# BatteryPoweredSchematic.net
KiCad netlist of a schematic drawn in Altium Designer
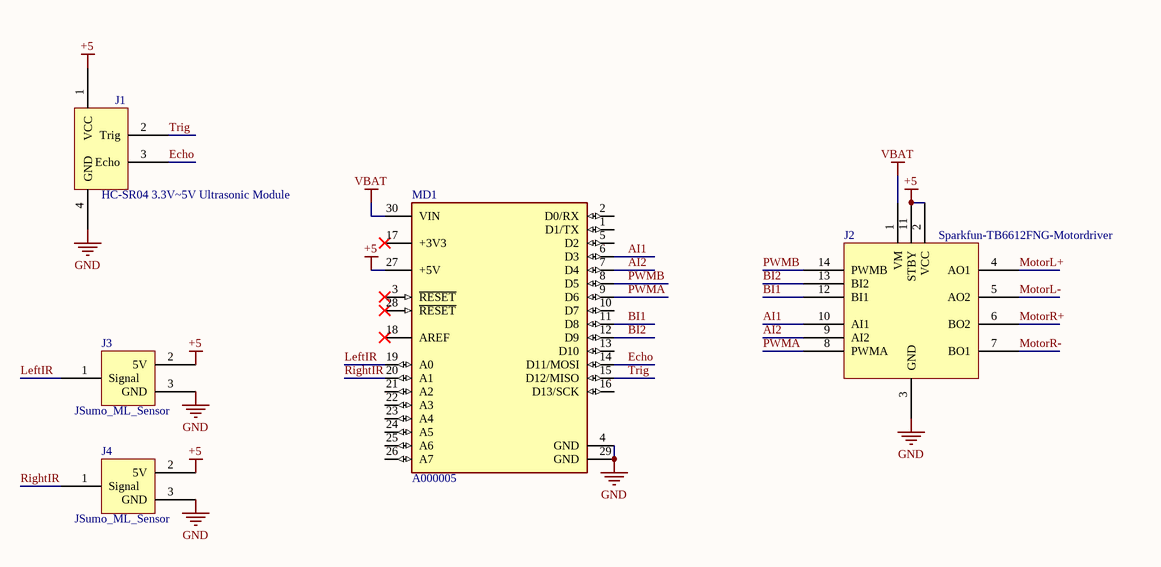
[diagram p0: BatteryPoweredSchematic.SchDoc]

(export (version "E")
  (design (tool "Eeschema 10.0.6"))
  (components
    (comp (ref "J1")
      (value "HC-SR04 3.3V~5V Ultrasonic Module")
      (libsource (lib "Matteo Jahshan") (part "HC-SR04 3.3V~5V Ultrasonic Module"))
    )
    (comp (ref "J2")
      (value "Sparkfun-TB6612FNG-Motordriver")
      (libsource (lib "Matteo Jahshan") (part "Sparkfun-TB6612FNG-Motordriver-Symbol-1"))
    )
    (comp (ref "J3")
      (value "JSumo_ML_Sensor")
      (libsource (lib "Matteo Jahshan") (part "JSumo_ML_Sensor-Symbol-1"))
    )
    (comp (ref "J4")
      (value "JSumo_ML_Sensor")
      (libsource (lib "Matteo Jahshan") (part "JSumo_ML_Sensor-Symbol-1"))
    )
    (comp (ref "MD1")
      (value "A000005")
      (footprint "FP-A000005-MFG")
      (description "ARDUINO NANO ATMEGA328 EVAL BRD")
      (libsource (lib "Altium Content Vault") (part "d190c066e99afd1c6882cf92e11b2cc"))
    )
  )
  (nets
    (net (code "1") (name "+5") (class "Default")
      (node (ref "J1") (pin "1") (pinfunction "VCC_1") (pintype "passive"))
      (node (ref "J2") (pin "11") (pinfunction "STBY_11") (pintype "passive"))
      (node (ref "J2") (pin "2") (pinfunction "VCC_2") (pintype "passive"))
      (node (ref "J3") (pin "2") (pinfunction "5V_2") (pintype "passive"))
      (node (ref "J4") (pin "2") (pinfunction "5V_2") (pintype "passive"))
      (node (ref "MD1") (pin "27") (pinfunction "+5V_27") (pintype "power_in"))
    )
    (net (code "2") (name "/AI1") (class "Default")
      (node (ref "J2") (pin "10") (pinfunction "AI1_10") (pintype "passive"))
      (node (ref "MD1") (pin "6") (pinfunction "D3_6") (pintype "bidirectional"))
    )
    (net (code "3") (name "/AI2") (class "Default")
      (node (ref "J2") (pin "9") (pinfunction "AI2_9") (pintype "passive"))
      (node (ref "MD1") (pin "7") (pinfunction "D4_7") (pintype "bidirectional"))
    )
    (net (code "4") (name "/BI1") (class "Default")
      (node (ref "J2") (pin "12") (pinfunction "BI1_12") (pintype "passive"))
      (node (ref "MD1") (pin "11") (pinfunction "D8_11") (pintype "bidirectional"))
    )
    (net (code "5") (name "/BI2") (class "Default")
      (node (ref "J2") (pin "13") (pinfunction "BI2_13") (pintype "passive"))
      (node (ref "MD1") (pin "12") (pinfunction "D9_12") (pintype "bidirectional"))
    )
    (net (code "6") (name "/Echo") (class "Default")
      (node (ref "J1") (pin "3") (pinfunction "Echo_3") (pintype "passive"))
      (node (ref "MD1") (pin "14") (pinfunction "D11/MOSI_14") (pintype "bidirectional"))
    )
    (net (code "7") (name "/LeftIR") (class "Default")
      (node (ref "J3") (pin "1") (pinfunction "Signal_1") (pintype "passive"))
      (node (ref "MD1") (pin "19") (pinfunction "A0_19") (pintype "bidirectional"))
    )
    (net (code "8") (name "/MotorL+") (class "Default")
      (node (ref "J2") (pin "4") (pinfunction "AO1_4") (pintype "passive"))
    )
    (net (code "9") (name "/MotorL-") (class "Default")
      (node (ref "J2") (pin "5") (pinfunction "AO2_5") (pintype "passive"))
    )
    (net (code "10") (name "/MotorR+") (class "Default")
      (node (ref "J2") (pin "6") (pinfunction "BO2_6") (pintype "passive"))
    )
    (net (code "11") (name "/MotorR-") (class "Default")
      (node (ref "J2") (pin "7") (pinfunction "BO1_7") (pintype "passive"))
    )
    (net (code "12") (name "/PWMA") (class "Default")
      (node (ref "J2") (pin "8") (pinfunction "PWMA_8") (pintype "passive"))
      (node (ref "MD1") (pin "9") (pinfunction "D6_9") (pintype "bidirectional"))
    )
    (net (code "13") (name "/PWMB") (class "Default")
      (node (ref "J2") (pin "14") (pinfunction "PWMB_14") (pintype "passive"))
      (node (ref "MD1") (pin "8") (pinfunction "D5_8") (pintype "bidirectional"))
    )
    (net (code "14") (name "/RightIR") (class "Default")
      (node (ref "J4") (pin "1") (pinfunction "Signal_1") (pintype "passive"))
      (node (ref "MD1") (pin "20") (pinfunction "A1_20") (pintype "bidirectional"))
    )
    (net (code "15") (name "/Trig") (class "Default")
      (node (ref "J1") (pin "2") (pinfunction "Trig_2") (pintype "passive"))
      (node (ref "MD1") (pin "15") (pinfunction "D12/MISO_15") (pintype "bidirectional"))
    )
    (net (code "16") (name "GND") (class "Default")
      (node (ref "J1") (pin "4") (pinfunction "GND_4") (pintype "passive"))
      (node (ref "J2") (pin "3") (pinfunction "GND_3") (pintype "passive"))
      (node (ref "J3") (pin "3") (pinfunction "GND_3") (pintype "passive"))
      (node (ref "J4") (pin "3") (pinfunction "GND_3") (pintype "passive"))
      (node (ref "MD1") (pin "29") (pinfunction "GND_29") (pintype "power_in"))
      (node (ref "MD1") (pin "4") (pinfunction "GND_4") (pintype "power_in"))
    )
    (net (code "17") (name "VBAT") (class "Default")
      (node (ref "J2") (pin "1") (pinfunction "VM_1") (pintype "passive"))
      (node (ref "MD1") (pin "30") (pinfunction "VIN_30") (pintype "power_in"))
    )
    (net (code "18") (name "unconnected-(MD1-+3V3-Pad17)") (class "Default")
      (node (ref "MD1") (pin "17") (pinfunction "+3V3_17") (pintype "power_in+no_connect"))
    )
    (net (code "19") (name "unconnected-(MD1-A2-Pad21)") (class "Default")
      (node (ref "MD1") (pin "21") (pinfunction "A2_21") (pintype "bidirectional"))
    )
    (net (code "20") (name "unconnected-(MD1-A3-Pad22)") (class "Default")
      (node (ref "MD1") (pin "22") (pinfunction "A3_22") (pintype "bidirectional"))
    )
    (net (code "21") (name "unconnected-(MD1-A4-Pad23)") (class "Default")
      (node (ref "MD1") (pin "23") (pinfunction "A4_23") (pintype "bidirectional"))
    )
    (net (code "22") (name "unconnected-(MD1-A5-Pad24)") (class "Default")
      (node (ref "MD1") (pin "24") (pinfunction "A5_24") (pintype "bidirectional"))
    )
    (net (code "23") (name "unconnected-(MD1-A6-Pad25)") (class "Default")
      (node (ref "MD1") (pin "25") (pinfunction "A6_25") (pintype "bidirectional"))
    )
    (net (code "24") (name "unconnected-(MD1-A7-Pad26)") (class "Default")
      (node (ref "MD1") (pin "26") (pinfunction "A7_26") (pintype "bidirectional"))
    )
    (net (code "25") (name "unconnected-(MD1-AREF-Pad18)") (class "Default")
      (node (ref "MD1") (pin "18") (pinfunction "AREF_18") (pintype "passive+no_connect"))
    )
    (net (code "26") (name "unconnected-(MD1-D0{slash}RX-Pad2)") (class "Default")
      (node (ref "MD1") (pin "2") (pinfunction "D0/RX_2") (pintype "bidirectional"))
    )
    (net (code "27") (name "unconnected-(MD1-D1{slash}TX-Pad1)") (class "Default")
      (node (ref "MD1") (pin "1") (pinfunction "D1/TX_1") (pintype "bidirectional"))
    )
    (net (code "28") (name "unconnected-(MD1-D2-Pad5)") (class "Default")
      (node (ref "MD1") (pin "5") (pinfunction "D2_5") (pintype "bidirectional"))
    )
    (net (code "29") (name "unconnected-(MD1-D7-Pad10)") (class "Default")
      (node (ref "MD1") (pin "10") (pinfunction "D7_10") (pintype "bidirectional"))
    )
    (net (code "30") (name "unconnected-(MD1-D10-Pad13)") (class "Default")
      (node (ref "MD1") (pin "13") (pinfunction "D10_13") (pintype "bidirectional"))
    )
    (net (code "31") (name "unconnected-(MD1-D13{slash}SCK-Pad16)") (class "Default")
      (node (ref "MD1") (pin "16") (pinfunction "D13/SCK_16") (pintype "bidirectional"))
    )
    (net (code "32") (name "unconnected-(MD1-~{RESET}-Pad3)") (class "Default")
      (node (ref "MD1") (pin "3") (pinfunction "~{RESET}_3") (pintype "input+no_connect"))
    )
    (net (code "33") (name "unconnected-(MD1-~{RESET}-Pad28)") (class "Default")
      (node (ref "MD1") (pin "28") (pinfunction "~{RESET}_28") (pintype "input+no_connect"))
    )
  )
)
